# HoloCubicMCUV02_220109.net
KiCad netlist of a schematic drawn in Altium Designer
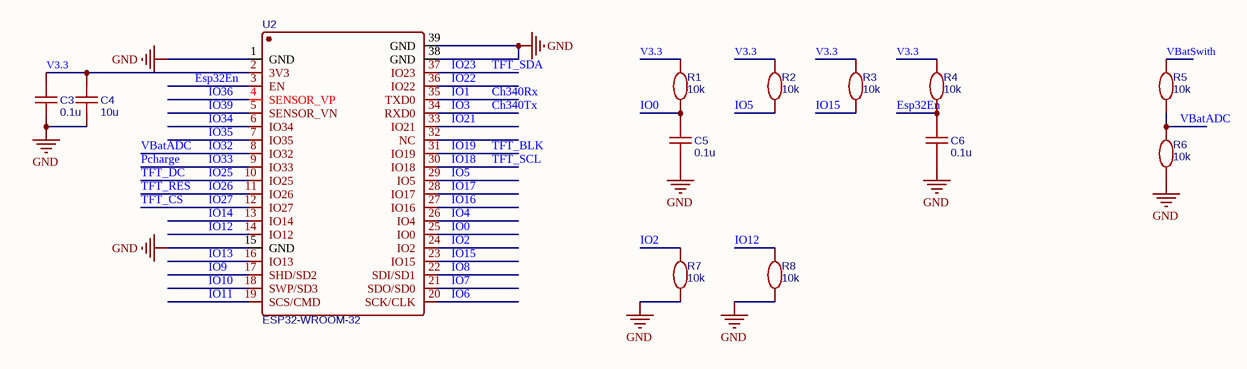
[diagram p0: HoloCubicMCUV02_220109.SchDoc]

(export (version "E")
  (design (tool "Eeschema 10.0.6"))
  (components
    (comp (ref "C3")
      (value "0.1u")
      (footprint "C0603")
      (fields (field (name "CONTRIBUTOR") "LCEDA_Lib"))
      (libsource (lib "altium-import") (part "root_1_0.1u_"))
    )
    (comp (ref "C4")
      (value "10u")
      (footprint "C0603")
      (fields (field (name "CONTRIBUTOR") "LCEDA_Lib"))
      (libsource (lib "altium-import") (part "root_1_0.1u_"))
    )
    (comp (ref "C5")
      (value "0.1u")
      (footprint "C0603")
      (fields (field (name "CONTRIBUTOR") "LCEDA_Lib"))
      (libsource (lib "altium-import") (part "root_1_0.1u_"))
    )
    (comp (ref "C6")
      (value "0.1u")
      (footprint "C0603")
      (fields (field (name "CONTRIBUTOR") "LCEDA_Lib"))
      (libsource (lib "altium-import") (part "root_1_0.1u_"))
    )
    (comp (ref "R1")
      (value "10k")
      (footprint "R0603")
      (fields (field (name "CONTRIBUTOR") "LCEDA_Lib"))
      (libsource (lib "altium-import") (part "root_1_10k_"))
    )
    (comp (ref "R2")
      (value "10k")
      (footprint "R0603")
      (fields (field (name "CONTRIBUTOR") "LCEDA_Lib"))
      (libsource (lib "altium-import") (part "root_1_10k_"))
    )
    (comp (ref "R3")
      (value "10k")
      (footprint "R0603")
      (fields (field (name "CONTRIBUTOR") "LCEDA_Lib"))
      (libsource (lib "altium-import") (part "root_1_10k_"))
    )
    (comp (ref "R4")
      (value "10k")
      (footprint "R0603")
      (fields (field (name "CONTRIBUTOR") "LCEDA_Lib"))
      (libsource (lib "altium-import") (part "root_1_10k_"))
    )
    (comp (ref "R5")
      (value "10k")
      (footprint "R0603")
      (fields (field (name "CONTRIBUTOR") "LCEDA_Lib"))
      (libsource (lib "altium-import") (part "root_1_10k_"))
    )
    (comp (ref "R6")
      (value "10k")
      (footprint "R0603")
      (fields (field (name "CONTRIBUTOR") "LCEDA_Lib"))
      (libsource (lib "altium-import") (part "root_1_10k_"))
    )
    (comp (ref "R7")
      (value "10k")
      (footprint "R0603")
      (fields (field (name "CONTRIBUTOR") "LCEDA_Lib"))
      (libsource (lib "altium-import") (part "root_1_10k_"))
    )
    (comp (ref "R8")
      (value "10k")
      (footprint "R0603")
      (fields (field (name "CONTRIBUTOR") "LCEDA_Lib"))
      (libsource (lib "altium-import") (part "root_1_10k_"))
    )
    (comp (ref "U2")
      (value "ESP32-WROOM-32")
      (footprint "WIFIM-SMD_ESP-32S")
      (fields (field (name "BOM_SUPPLIER PART") "C82899") (field (name "CONTRIBUTOR") "LCSC"))
      (libsource (lib "ZtYADLib") (part "ESP32-WROOM-32"))
    )
  )
  (nets
    (net (code "1") (name "/Ch340Rx") (class "Default")
      (node (ref "U2") (pin "35") (pinfunction "TXD0_35") (pintype "passive"))
    )
    (net (code "2") (name "/Ch340Tx") (class "Default")
      (node (ref "U2") (pin "34") (pinfunction "RXD0_34") (pintype "passive"))
    )
    (net (code "3") (name "/Esp32En") (class "Default")
      (node (ref "C6") (pin "2") (pinfunction "2_2") (pintype "passive"))
      (node (ref "R4") (pin "1") (pinfunction "1_1") (pintype "passive"))
      (node (ref "U2") (pin "3") (pinfunction "EN_3") (pintype "passive"))
    )
    (net (code "4") (name "/IO0") (class "Default")
      (node (ref "C5") (pin "2") (pinfunction "2_2") (pintype "passive"))
      (node (ref "R1") (pin "1") (pinfunction "1_1") (pintype "passive"))
      (node (ref "U2") (pin "25") (pinfunction "IO0_25") (pintype "passive"))
    )
    (net (code "5") (name "/IO2") (class "Default")
      (node (ref "R7") (pin "2") (pinfunction "2_2") (pintype "passive"))
      (node (ref "U2") (pin "24") (pinfunction "IO2_24") (pintype "passive"))
    )
    (net (code "6") (name "/IO4") (class "Default")
      (node (ref "U2") (pin "26") (pinfunction "IO4_26") (pintype "passive"))
    )
    (net (code "7") (name "/IO5") (class "Default")
      (node (ref "R2") (pin "1") (pinfunction "1_1") (pintype "passive"))
      (node (ref "U2") (pin "29") (pinfunction "IO5_29") (pintype "passive"))
    )
    (net (code "8") (name "/IO6") (class "Default")
      (node (ref "U2") (pin "20") (pinfunction "SCK/CLK_20") (pintype "passive"))
    )
    (net (code "9") (name "/IO7") (class "Default")
      (node (ref "U2") (pin "21") (pinfunction "SDO/SD0_21") (pintype "passive"))
    )
    (net (code "10") (name "/IO8") (class "Default")
      (node (ref "U2") (pin "22") (pinfunction "SDI/SD1_22") (pintype "passive"))
    )
    (net (code "11") (name "/IO9") (class "Default")
      (node (ref "U2") (pin "17") (pinfunction "SHD/SD2_17") (pintype "passive"))
    )
    (net (code "12") (name "/IO10") (class "Default")
      (node (ref "U2") (pin "18") (pinfunction "SWP/SD3_18") (pintype "passive"))
    )
    (net (code "13") (name "/IO11") (class "Default")
      (node (ref "U2") (pin "19") (pinfunction "SCS/CMD_19") (pintype "passive"))
    )
    (net (code "14") (name "/IO12") (class "Default")
      (node (ref "R8") (pin "2") (pinfunction "2_2") (pintype "passive"))
      (node (ref "U2") (pin "14") (pinfunction "IO12_14") (pintype "passive"))
    )
    (net (code "15") (name "/IO13") (class "Default")
      (node (ref "U2") (pin "16") (pinfunction "IO13_16") (pintype "passive"))
    )
    (net (code "16") (name "/IO14") (class "Default")
      (node (ref "U2") (pin "13") (pinfunction "IO14_13") (pintype "passive"))
    )
    (net (code "17") (name "/IO15") (class "Default")
      (node (ref "R3") (pin "1") (pinfunction "1_1") (pintype "passive"))
      (node (ref "U2") (pin "23") (pinfunction "IO15_23") (pintype "passive"))
    )
    (net (code "18") (name "/IO16") (class "Default")
      (node (ref "U2") (pin "27") (pinfunction "IO16_27") (pintype "passive"))
    )
    (net (code "19") (name "/IO17") (class "Default")
      (node (ref "U2") (pin "28") (pinfunction "IO17_28") (pintype "passive"))
    )
    (net (code "20") (name "/IO18") (class "Default")
      (node (ref "U2") (pin "30") (pinfunction "IO18_30") (pintype "passive"))
    )
    (net (code "21") (name "/IO19") (class "Default")
      (node (ref "U2") (pin "31") (pinfunction "IO19_31") (pintype "passive"))
    )
    (net (code "22") (name "/IO21") (class "Default")
      (node (ref "U2") (pin "33") (pinfunction "IO21_33") (pintype "passive"))
    )
    (net (code "23") (name "/IO22") (class "Default")
      (node (ref "U2") (pin "36") (pinfunction "IO22_36") (pintype "passive"))
    )
    (net (code "24") (name "/IO23") (class "Default")
      (node (ref "U2") (pin "37") (pinfunction "IO23_37") (pintype "passive"))
    )
    (net (code "25") (name "/IO25") (class "Default")
      (node (ref "U2") (pin "10") (pinfunction "IO25_10") (pintype "passive"))
    )
    (net (code "26") (name "/IO26") (class "Default")
      (node (ref "U2") (pin "11") (pinfunction "IO26_11") (pintype "passive"))
    )
    (net (code "27") (name "/IO27") (class "Default")
      (node (ref "U2") (pin "12") (pinfunction "IO27_12") (pintype "passive"))
    )
    (net (code "28") (name "/IO32") (class "Default")
      (node (ref "R5") (pin "1") (pinfunction "1_1") (pintype "passive"))
      (node (ref "R6") (pin "2") (pinfunction "2_2") (pintype "passive"))
      (node (ref "U2") (pin "8") (pinfunction "IO32_8") (pintype "passive"))
    )
    (net (code "29") (name "/IO33") (class "Default")
      (node (ref "U2") (pin "9") (pinfunction "IO33_9") (pintype "passive"))
    )
    (net (code "30") (name "/IO34") (class "Default")
      (node (ref "U2") (pin "6") (pinfunction "IO34_6") (pintype "passive"))
    )
    (net (code "31") (name "/IO35") (class "Default")
      (node (ref "U2") (pin "7") (pinfunction "IO35_7") (pintype "passive"))
    )
    (net (code "32") (name "/IO36") (class "Default")
      (node (ref "U2") (pin "4") (pinfunction "SENSOR_VP_4") (pintype "passive"))
    )
    (net (code "33") (name "/IO39") (class "Default")
      (node (ref "U2") (pin "5") (pinfunction "SENSOR_VN_5") (pintype "passive"))
    )
    (net (code "34") (name "/V3.3") (class "Default")
      (node (ref "C3") (pin "2") (pinfunction "2_2") (pintype "passive"))
      (node (ref "C4") (pin "2") (pinfunction "2_2") (pintype "passive"))
      (node (ref "R1") (pin "2") (pinfunction "2_2") (pintype "passive"))
      (node (ref "R2") (pin "2") (pinfunction "2_2") (pintype "passive"))
      (node (ref "R3") (pin "2") (pinfunction "2_2") (pintype "passive"))
      (node (ref "R4") (pin "2") (pinfunction "2_2") (pintype "passive"))
      (node (ref "U2") (pin "2") (pinfunction "3V3_2") (pintype "passive"))
    )
    (net (code "35") (name "/VBatSwith") (class "Default")
      (node (ref "R5") (pin "2") (pinfunction "2_2") (pintype "passive"))
    )
    (net (code "36") (name "GND") (class "Default")
      (node (ref "C3") (pin "1") (pinfunction "1_1") (pintype "passive"))
      (node (ref "C4") (pin "1") (pinfunction "1_1") (pintype "passive"))
      (node (ref "C5") (pin "1") (pinfunction "1_1") (pintype "passive"))
      (node (ref "C6") (pin "1") (pinfunction "1_1") (pintype "passive"))
      (node (ref "R6") (pin "1") (pinfunction "1_1") (pintype "passive"))
      (node (ref "R7") (pin "1") (pinfunction "1_1") (pintype "passive"))
      (node (ref "R8") (pin "1") (pinfunction "1_1") (pintype "passive"))
      (node (ref "U2") (pin "1") (pinfunction "GND_1") (pintype "passive"))
      (node (ref "U2") (pin "15") (pinfunction "GND_15") (pintype "passive"))
      (node (ref "U2") (pin "38") (pinfunction "GND_38") (pintype "passive"))
      (node (ref "U2") (pin "39") (pinfunction "GND_39") (pintype "passive"))
    )
    (net (code "37") (name "unconnected-(U2-NC-Pad32)") (class "Default")
      (node (ref "U2") (pin "32") (pinfunction "NC_32") (pintype "passive"))
    )
  )
)
